# Smart_Plant.net
KiCad netlist of a schematic drawn in EAGLE
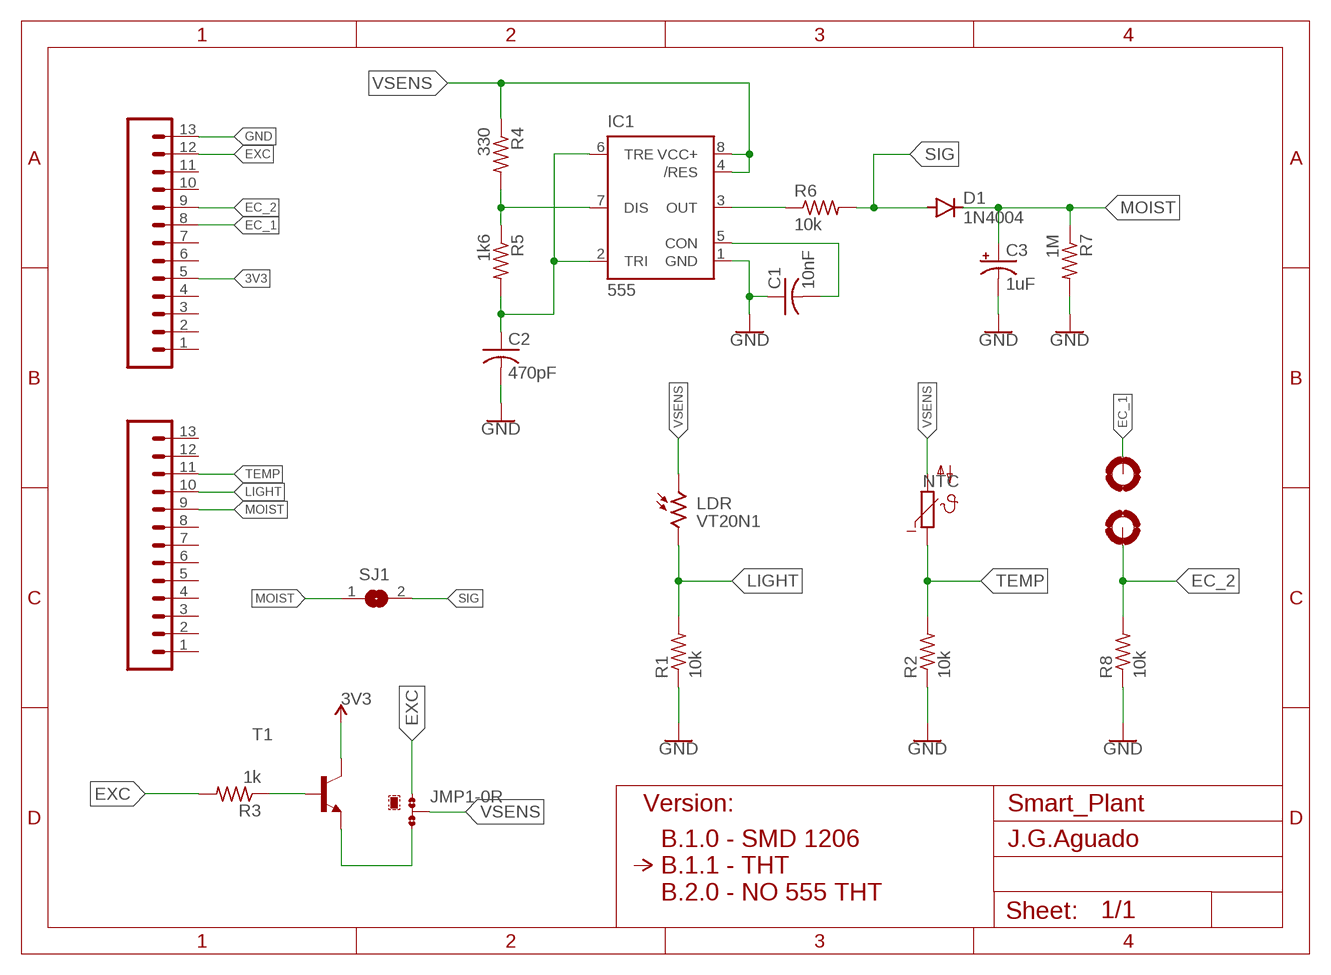
[diagram p0: schematic, sheet 1]

(export (version "E")
  (design (tool "Eeschema 10.0.6"))
  (components
    (comp (ref "C1")
      (value "10nF")
      (footprint "eagle-import:C050-025X075")
      (libsource (lib "eagle-import") (part "C-US050-025X075"))
    )
    (comp (ref "C2")
      (value "470pF")
      (footprint "eagle-import:C050-025X075")
      (libsource (lib "eagle-import") (part "C-US050-025X075"))
    )
    (comp (ref "C3")
      (value "1uF")
      (footprint "eagle-import:E2,5-5")
      (libsource (lib "eagle-import") (part "CPOL-USE2.5-5"))
    )
    (comp (ref "D1")
      (value "1N4004")
      (footprint "eagle-import:DO41-10")
      (libsource (lib "eagle-import") (part "1N4004"))
    )
    (comp (ref "H1")
      (value "MOUNT-PAD-ROUND3.0")
      (footprint "eagle-import:3,0-PAD")
      (libsource (lib "eagle-import") (part "MOUNT-PAD-ROUND3.0"))
    )
    (comp (ref "H2")
      (value "MOUNT-PAD-ROUND3.0")
      (footprint "eagle-import:3,0-PAD")
      (libsource (lib "eagle-import") (part "MOUNT-PAD-ROUND3.0"))
    )
    (comp (ref "IC1")
      (value "555")
      (footprint "eagle-import:DIP08-KIT")
      (libsource (lib "eagle-import") (part "555KIT"))
    )
    (comp (ref "JMP1")
      (value "0R-JUMPB")
      (footprint "eagle-import:B0R-JMP")
      (libsource (lib "eagle-import") (part "0R-JUMPB"))
    )
    (comp (ref "JP1")
      (value "CONN_13")
      (footprint "eagle-import:1X13")
      (libsource (lib "eagle-import") (part "CONN_13"))
    )
    (comp (ref "JP2")
      (value "CONN_13")
      (footprint "eagle-import:1X13")
      (libsource (lib "eagle-import") (part "CONN_13"))
    )
    (comp (ref "LDR")
      (value "VT20N1")
      (footprint "eagle-import:TO46-VT200")
      (libsource (lib "eagle-import") (part "VT20N1"))
    )
    (comp (ref "NTC")
      (value "R1206")
      (footprint "eagle-import:P640")
      (libsource (lib "eagle-import") (part "NTC640"))
    )
    (comp (ref "R1")
      (value "10k")
      (footprint "eagle-import:0207_10")
      (libsource (lib "eagle-import") (part "R-US_0207/10"))
    )
    (comp (ref "R2")
      (value "10k")
      (footprint "eagle-import:0207_10")
      (libsource (lib "eagle-import") (part "R-US_0207/10"))
    )
    (comp (ref "R3")
      (value "1k")
      (footprint "eagle-import:0207_10")
      (libsource (lib "eagle-import") (part "R-US_0207/10"))
    )
    (comp (ref "R4")
      (value "330")
      (footprint "eagle-import:0207_10")
      (libsource (lib "eagle-import") (part "R-US_0207/10"))
    )
    (comp (ref "R5")
      (value "1k6")
      (footprint "eagle-import:0207_10")
      (libsource (lib "eagle-import") (part "R-US_0207/10"))
    )
    (comp (ref "R6")
      (value "10k")
      (footprint "eagle-import:0207_10")
      (libsource (lib "eagle-import") (part "R-US_0207/10"))
    )
    (comp (ref "R7")
      (value "1M")
      (footprint "eagle-import:0207_10")
      (libsource (lib "eagle-import") (part "R-US_0207/10"))
    )
    (comp (ref "R8")
      (value "10k")
      (footprint "eagle-import:0207_10")
      (libsource (lib "eagle-import") (part "R-US_0207/10"))
    )
    (comp (ref "SJ1") (value "SJ") (footprint "eagle-import:SJ") (libsource (lib "eagle-import") (part "SJ")))
    (comp (ref "T1")
      (value "-NPN-TO92-ECB")
      (footprint "eagle-import:TO92-ECB")
      (libsource (lib "eagle-import") (part "-NPN-TO92-ECB"))
    )
  )
  (nets
    (net (code "1") (name "3V3") (class "Default")
      (node (ref "JP1") (pin "5") (pinfunction "5_5") (pintype "passive"))
      (node (ref "T1") (pin "C") (pinfunction "C_C") (pintype "passive"))
    )
    (net (code "2") (name "EC_1") (class "Default")
      (node (ref "H1") (pin "B3,0") (pinfunction "MOUNT_B3,0") (pintype "passive"))
      (node (ref "JP1") (pin "8") (pinfunction "8_8") (pintype "passive"))
    )
    (net (code "3") (name "EC_2") (class "Default")
      (node (ref "H2") (pin "B3,0") (pinfunction "MOUNT_B3,0") (pintype "passive"))
      (node (ref "JP1") (pin "9") (pinfunction "9_9") (pintype "passive"))
      (node (ref "R8") (pin "2") (pinfunction "2_2") (pintype "passive"))
    )
    (net (code "4") (name "EXC") (class "Default")
      (node (ref "JMP1") (pin "1") (pinfunction "1_1") (pintype "passive"))
      (node (ref "JP1") (pin "12") (pinfunction "12_12") (pintype "passive"))
      (node (ref "R3") (pin "2") (pinfunction "2_2") (pintype "passive"))
    )
    (net (code "5") (name "GND") (class "Default")
      (node (ref "C1") (pin "1") (pinfunction "1_1") (pintype "passive"))
      (node (ref "C2") (pin "2") (pinfunction "2_2") (pintype "passive"))
      (node (ref "C3") (pin "-") (pinfunction "-_-") (pintype "passive"))
      (node (ref "IC1") (pin "1") (pinfunction "GND_1") (pintype "power_in"))
      (node (ref "JP1") (pin "13") (pinfunction "13_13") (pintype "passive"))
      (node (ref "R1") (pin "1") (pinfunction "1_1") (pintype "passive"))
      (node (ref "R2") (pin "1") (pinfunction "1_1") (pintype "passive"))
      (node (ref "R7") (pin "2") (pinfunction "2_2") (pintype "passive"))
      (node (ref "R8") (pin "1") (pinfunction "1_1") (pintype "passive"))
    )
    (net (code "6") (name "LIGHT") (class "Default")
      (node (ref "JP2") (pin "10") (pinfunction "10_10") (pintype "passive"))
      (node (ref "LDR") (pin "2") (pinfunction "2_2") (pintype "passive"))
      (node (ref "R1") (pin "2") (pinfunction "2_2") (pintype "passive"))
    )
    (net (code "7") (name "MOIST") (class "Default")
      (node (ref "C3") (pin "+") (pinfunction "+_+") (pintype "passive"))
      (node (ref "D1") (pin "C") (pinfunction "C_C") (pintype "passive"))
      (node (ref "JP2") (pin "9") (pinfunction "9_9") (pintype "passive"))
      (node (ref "R7") (pin "1") (pinfunction "1_1") (pintype "passive"))
      (node (ref "SJ1") (pin "1") (pinfunction "1_1") (pintype "passive"))
    )
    (net (code "8") (name "Net-(IC1-CON)") (class "Default")
      (node (ref "C1") (pin "2") (pinfunction "2_2") (pintype "passive"))
      (node (ref "IC1") (pin "5") (pinfunction "CON_5") (pintype "input"))
    )
    (net (code "9") (name "Net-(IC1-DIS)") (class "Default")
      (node (ref "IC1") (pin "7") (pinfunction "DIS_7") (pintype "input"))
      (node (ref "R4") (pin "2") (pinfunction "2_2") (pintype "passive"))
      (node (ref "R5") (pin "1") (pinfunction "1_1") (pintype "passive"))
    )
    (net (code "10") (name "Net-(IC1-OUT)") (class "Default")
      (node (ref "IC1") (pin "3") (pinfunction "OUT_3") (pintype "output"))
      (node (ref "R6") (pin "1") (pinfunction "1_1") (pintype "passive"))
    )
    (net (code "11") (name "Net-(IC1-TRE)") (class "Default")
      (node (ref "C2") (pin "1") (pinfunction "1_1") (pintype "passive"))
      (node (ref "IC1") (pin "2") (pinfunction "TRI_2") (pintype "input"))
      (node (ref "IC1") (pin "6") (pinfunction "TRE_6") (pintype "input"))
      (node (ref "R5") (pin "2") (pinfunction "2_2") (pintype "passive"))
    )
    (net (code "12") (name "Net-(JMP1-Pad3)") (class "Default")
      (node (ref "JMP1") (pin "3") (pinfunction "3_3") (pintype "passive"))
      (node (ref "T1") (pin "E") (pinfunction "E_E") (pintype "passive"))
    )
    (net (code "13") (name "Net-(R3-Pad1)") (class "Default")
      (node (ref "R3") (pin "1") (pinfunction "1_1") (pintype "passive"))
      (node (ref "T1") (pin "B") (pinfunction "B_B") (pintype "passive"))
    )
    (net (code "14") (name "SIG") (class "Default")
      (node (ref "D1") (pin "A") (pinfunction "A_A") (pintype "passive"))
      (node (ref "R6") (pin "2") (pinfunction "2_2") (pintype "passive"))
      (node (ref "SJ1") (pin "2") (pinfunction "2_2") (pintype "passive"))
    )
    (net (code "15") (name "TEMP") (class "Default")
      (node (ref "JP2") (pin "11") (pinfunction "11_11") (pintype "passive"))
      (node (ref "NTC") (pin "1") (pinfunction "1_1") (pintype "passive"))
      (node (ref "R2") (pin "2") (pinfunction "2_2") (pintype "passive"))
    )
    (net (code "16") (name "VSENS") (class "Default")
      (node (ref "IC1") (pin "4") (pinfunction "/RES_4") (pintype "input"))
      (node (ref "IC1") (pin "8") (pinfunction "VCC+_8") (pintype "power_in"))
      (node (ref "JMP1") (pin "2") (pinfunction "2_2") (pintype "passive"))
      (node (ref "LDR") (pin "1") (pinfunction "1_1") (pintype "passive"))
      (node (ref "NTC") (pin "2") (pinfunction "2_2") (pintype "passive"))
      (node (ref "R4") (pin "1") (pinfunction "1_1") (pintype "passive"))
    )
    (net (code "17") (name "unconnected-(JP1-Pad1)") (class "Default")
      (node (ref "JP1") (pin "1") (pinfunction "1_1") (pintype "passive"))
    )
    (net (code "18") (name "unconnected-(JP1-Pad2)") (class "Default")
      (node (ref "JP1") (pin "2") (pinfunction "2_2") (pintype "passive"))
    )
    (net (code "19") (name "unconnected-(JP1-Pad3)") (class "Default")
      (node (ref "JP1") (pin "3") (pinfunction "3_3") (pintype "passive"))
    )
    (net (code "20") (name "unconnected-(JP1-Pad4)") (class "Default")
      (node (ref "JP1") (pin "4") (pinfunction "4_4") (pintype "passive"))
    )
    (net (code "21") (name "unconnected-(JP1-Pad6)") (class "Default")
      (node (ref "JP1") (pin "6") (pinfunction "6_6") (pintype "passive"))
    )
    (net (code "22") (name "unconnected-(JP1-Pad7)") (class "Default")
      (node (ref "JP1") (pin "7") (pinfunction "7_7") (pintype "passive"))
    )
    (net (code "23") (name "unconnected-(JP1-Pad10)") (class "Default")
      (node (ref "JP1") (pin "10") (pinfunction "10_10") (pintype "passive"))
    )
    (net (code "24") (name "unconnected-(JP1-Pad11)") (class "Default")
      (node (ref "JP1") (pin "11") (pinfunction "11_11") (pintype "passive"))
    )
    (net (code "25") (name "unconnected-(JP2-Pad1)") (class "Default")
      (node (ref "JP2") (pin "1") (pinfunction "1_1") (pintype "passive"))
    )
    (net (code "26") (name "unconnected-(JP2-Pad2)") (class "Default")
      (node (ref "JP2") (pin "2") (pinfunction "2_2") (pintype "passive"))
    )
    (net (code "27") (name "unconnected-(JP2-Pad3)") (class "Default")
      (node (ref "JP2") (pin "3") (pinfunction "3_3") (pintype "passive"))
    )
    (net (code "28") (name "unconnected-(JP2-Pad4)") (class "Default")
      (node (ref "JP2") (pin "4") (pinfunction "4_4") (pintype "passive"))
    )
    (net (code "29") (name "unconnected-(JP2-Pad5)") (class "Default")
      (node (ref "JP2") (pin "5") (pinfunction "5_5") (pintype "passive"))
    )
    (net (code "30") (name "unconnected-(JP2-Pad6)") (class "Default")
      (node (ref "JP2") (pin "6") (pinfunction "6_6") (pintype "passive"))
    )
    (net (code "31") (name "unconnected-(JP2-Pad7)") (class "Default")
      (node (ref "JP2") (pin "7") (pinfunction "7_7") (pintype "passive"))
    )
    (net (code "32") (name "unconnected-(JP2-Pad8)") (class "Default")
      (node (ref "JP2") (pin "8") (pinfunction "8_8") (pintype "passive"))
    )
    (net (code "33") (name "unconnected-(JP2-Pad12)") (class "Default")
      (node (ref "JP2") (pin "12") (pinfunction "12_12") (pintype "passive"))
    )
    (net (code "34") (name "unconnected-(JP2-Pad13)") (class "Default")
      (node (ref "JP2") (pin "13") (pinfunction "13_13") (pintype "passive"))
    )
  )
)
